# Power.net
KiCad netlist of a schematic drawn in Altium Designer
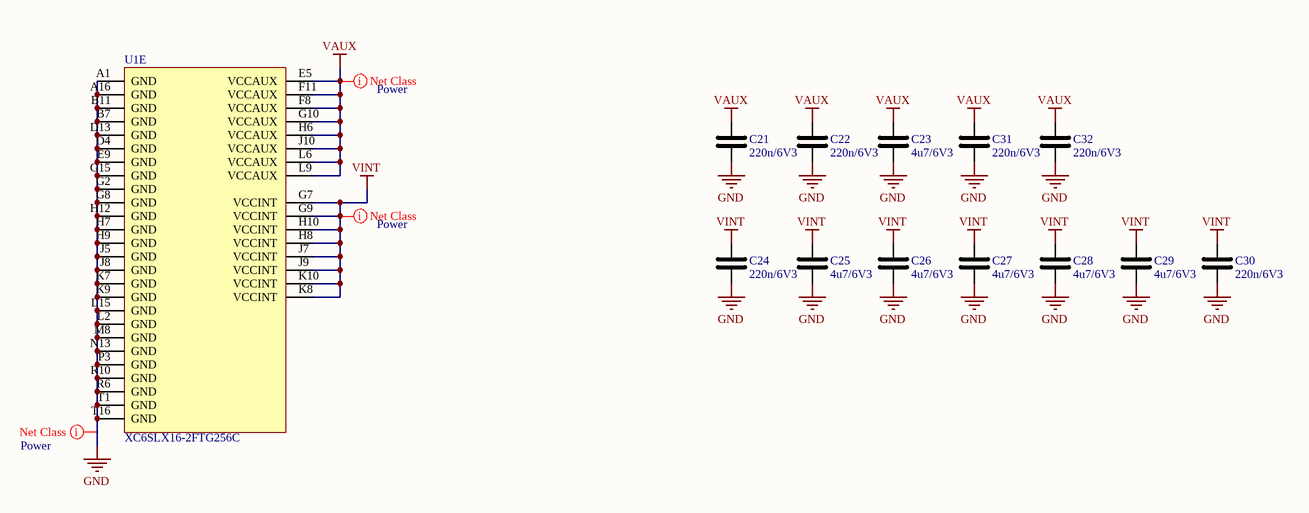
[diagram p0: Power.SchDoc]

(export (version "E")
  (design (tool "Eeschema 10.0.6"))
  (components
    (comp (ref "C21") (value "220n/6V3") (footprint "C0402_N") (libsource (lib "niceCircuits") (part "C")))
    (comp (ref "C22") (value "220n/6V3") (footprint "C0402_N") (libsource (lib "niceCircuits") (part "C")))
    (comp (ref "C23") (value "4u7/6V3") (footprint "C0805_N") (libsource (lib "niceCircuits") (part "C")))
    (comp (ref "C24") (value "220n/6V3") (footprint "C0402_N") (libsource (lib "niceCircuits") (part "C")))
    (comp (ref "C25") (value "4u7/6V3") (footprint "C0805_N") (libsource (lib "niceCircuits") (part "C")))
    (comp (ref "C26") (value "4u7/6V3") (footprint "C0805_N") (libsource (lib "niceCircuits") (part "C")))
    (comp (ref "C27") (value "4u7/6V3") (footprint "C0805_N") (libsource (lib "niceCircuits") (part "C")))
    (comp (ref "C28") (value "4u7/6V3") (footprint "C0805_N") (libsource (lib "niceCircuits") (part "C")))
    (comp (ref "C29") (value "4u7/6V3") (footprint "C0805_N") (libsource (lib "niceCircuits") (part "C")))
    (comp (ref "C30") (value "220n/6V3") (footprint "C0402_N") (libsource (lib "niceCircuits") (part "C")))
    (comp (ref "C31") (value "220n/6V3") (footprint "C0402_N") (libsource (lib "niceCircuits") (part "C")))
    (comp (ref "C32") (value "220n/6V3") (footprint "C0402_N") (libsource (lib "niceCircuits") (part "C")))
    (comp (ref "U1")
      (value "XC6SLX16-2FTG256C")
      (footprint "Xilinx_FT256_L")
      (libsource (lib "niceCircuits") (part "XC6SLX16-2FTG256C"))
    )
  )
  (nets
    (net (code "1") (name "GND") (class "Default")
      (node (ref "C21") (pin "1") (pinfunction "1_1") (pintype "passive"))
      (node (ref "C22") (pin "1") (pinfunction "1_1") (pintype "passive"))
      (node (ref "C23") (pin "1") (pinfunction "1_1") (pintype "passive"))
      (node (ref "C24") (pin "1") (pinfunction "1_1") (pintype "passive"))
      (node (ref "C25") (pin "1") (pinfunction "1_1") (pintype "passive"))
      (node (ref "C26") (pin "1") (pinfunction "1_1") (pintype "passive"))
      (node (ref "C27") (pin "1") (pinfunction "1_1") (pintype "passive"))
      (node (ref "C28") (pin "1") (pinfunction "1_1") (pintype "passive"))
      (node (ref "C29") (pin "1") (pinfunction "1_1") (pintype "passive"))
      (node (ref "C30") (pin "1") (pinfunction "1_1") (pintype "passive"))
      (node (ref "C31") (pin "1") (pinfunction "1_1") (pintype "passive"))
      (node (ref "C32") (pin "1") (pinfunction "1_1") (pintype "passive"))
      (node (ref "U1") (pin "A1") (pinfunction "GND_A1") (pintype "power_in"))
      (node (ref "U1") (pin "A16") (pinfunction "GND_A16") (pintype "power_in"))
      (node (ref "U1") (pin "B11") (pinfunction "GND_B11") (pintype "power_in"))
      (node (ref "U1") (pin "B7") (pinfunction "GND_B7") (pintype "power_in"))
      (node (ref "U1") (pin "D13") (pinfunction "GND_D13") (pintype "power_in"))
      (node (ref "U1") (pin "D4") (pinfunction "GND_D4") (pintype "power_in"))
      (node (ref "U1") (pin "E9") (pinfunction "GND_E9") (pintype "power_in"))
      (node (ref "U1") (pin "G15") (pinfunction "GND_G15") (pintype "power_in"))
      (node (ref "U1") (pin "G2") (pinfunction "GND_G2") (pintype "power_in"))
      (node (ref "U1") (pin "G8") (pinfunction "GND_G8") (pintype "power_in"))
      (node (ref "U1") (pin "H12") (pinfunction "GND_H12") (pintype "power_in"))
      (node (ref "U1") (pin "H7") (pinfunction "GND_H7") (pintype "power_in"))
      (node (ref "U1") (pin "H9") (pinfunction "GND_H9") (pintype "power_in"))
      (node (ref "U1") (pin "J5") (pinfunction "GND_J5") (pintype "power_in"))
      (node (ref "U1") (pin "J8") (pinfunction "GND_J8") (pintype "power_in"))
      (node (ref "U1") (pin "K7") (pinfunction "GND_K7") (pintype "power_in"))
      (node (ref "U1") (pin "K9") (pinfunction "GND_K9") (pintype "power_in"))
      (node (ref "U1") (pin "L15") (pinfunction "GND_L15") (pintype "power_in"))
      (node (ref "U1") (pin "L2") (pinfunction "GND_L2") (pintype "power_in"))
      (node (ref "U1") (pin "M8") (pinfunction "GND_M8") (pintype "power_in"))
      (node (ref "U1") (pin "N13") (pinfunction "GND_N13") (pintype "power_in"))
      (node (ref "U1") (pin "P3") (pinfunction "GND_P3") (pintype "power_in"))
      (node (ref "U1") (pin "R10") (pinfunction "GND_R10") (pintype "power_in"))
      (node (ref "U1") (pin "R6") (pinfunction "GND_R6") (pintype "power_in"))
      (node (ref "U1") (pin "T1") (pinfunction "GND_T1") (pintype "power_in"))
      (node (ref "U1") (pin "T16") (pinfunction "GND_T16") (pintype "power_in"))
    )
    (net (code "2") (name "VAUX") (class "Default")
      (node (ref "C21") (pin "2") (pinfunction "2_2") (pintype "passive"))
      (node (ref "C22") (pin "2") (pinfunction "2_2") (pintype "passive"))
      (node (ref "C23") (pin "2") (pinfunction "2_2") (pintype "passive"))
      (node (ref "C31") (pin "2") (pinfunction "2_2") (pintype "passive"))
      (node (ref "C32") (pin "2") (pinfunction "2_2") (pintype "passive"))
      (node (ref "U1") (pin "E5") (pinfunction "VCCAUX_E5") (pintype "power_in"))
      (node (ref "U1") (pin "F11") (pinfunction "VCCAUX_F11") (pintype "power_in"))
      (node (ref "U1") (pin "F8") (pinfunction "VCCAUX_F8") (pintype "power_in"))
      (node (ref "U1") (pin "G10") (pinfunction "VCCAUX_G10") (pintype "power_in"))
      (node (ref "U1") (pin "H6") (pinfunction "VCCAUX_H6") (pintype "power_in"))
      (node (ref "U1") (pin "J10") (pinfunction "VCCAUX_J10") (pintype "power_in"))
      (node (ref "U1") (pin "L6") (pinfunction "VCCAUX_L6") (pintype "power_in"))
      (node (ref "U1") (pin "L9") (pinfunction "VCCAUX_L9") (pintype "power_in"))
    )
    (net (code "3") (name "VINT") (class "Default")
      (node (ref "C24") (pin "2") (pinfunction "2_2") (pintype "passive"))
      (node (ref "C25") (pin "2") (pinfunction "2_2") (pintype "passive"))
      (node (ref "C26") (pin "2") (pinfunction "2_2") (pintype "passive"))
      (node (ref "C27") (pin "2") (pinfunction "2_2") (pintype "passive"))
      (node (ref "C28") (pin "2") (pinfunction "2_2") (pintype "passive"))
      (node (ref "C29") (pin "2") (pinfunction "2_2") (pintype "passive"))
      (node (ref "C30") (pin "2") (pinfunction "2_2") (pintype "passive"))
      (node (ref "U1") (pin "G7") (pinfunction "VCCINT_G7") (pintype "power_in"))
      (node (ref "U1") (pin "G9") (pinfunction "VCCINT_G9") (pintype "power_in"))
      (node (ref "U1") (pin "H10") (pinfunction "VCCINT_H10") (pintype "power_in"))
      (node (ref "U1") (pin "H8") (pinfunction "VCCINT_H8") (pintype "power_in"))
      (node (ref "U1") (pin "J7") (pinfunction "VCCINT_J7") (pintype "power_in"))
      (node (ref "U1") (pin "J9") (pinfunction "VCCINT_J9") (pintype "power_in"))
      (node (ref "U1") (pin "K10") (pinfunction "VCCINT_K10") (pintype "power_in"))
      (node (ref "U1") (pin "K8") (pinfunction "VCCINT_K8") (pintype "power_in"))
    )
  )
)
